# SCH_MODULO_CO2_Ver_1_0__2023-02-25.net
KiCad netlist of a schematic drawn in EasyEDA
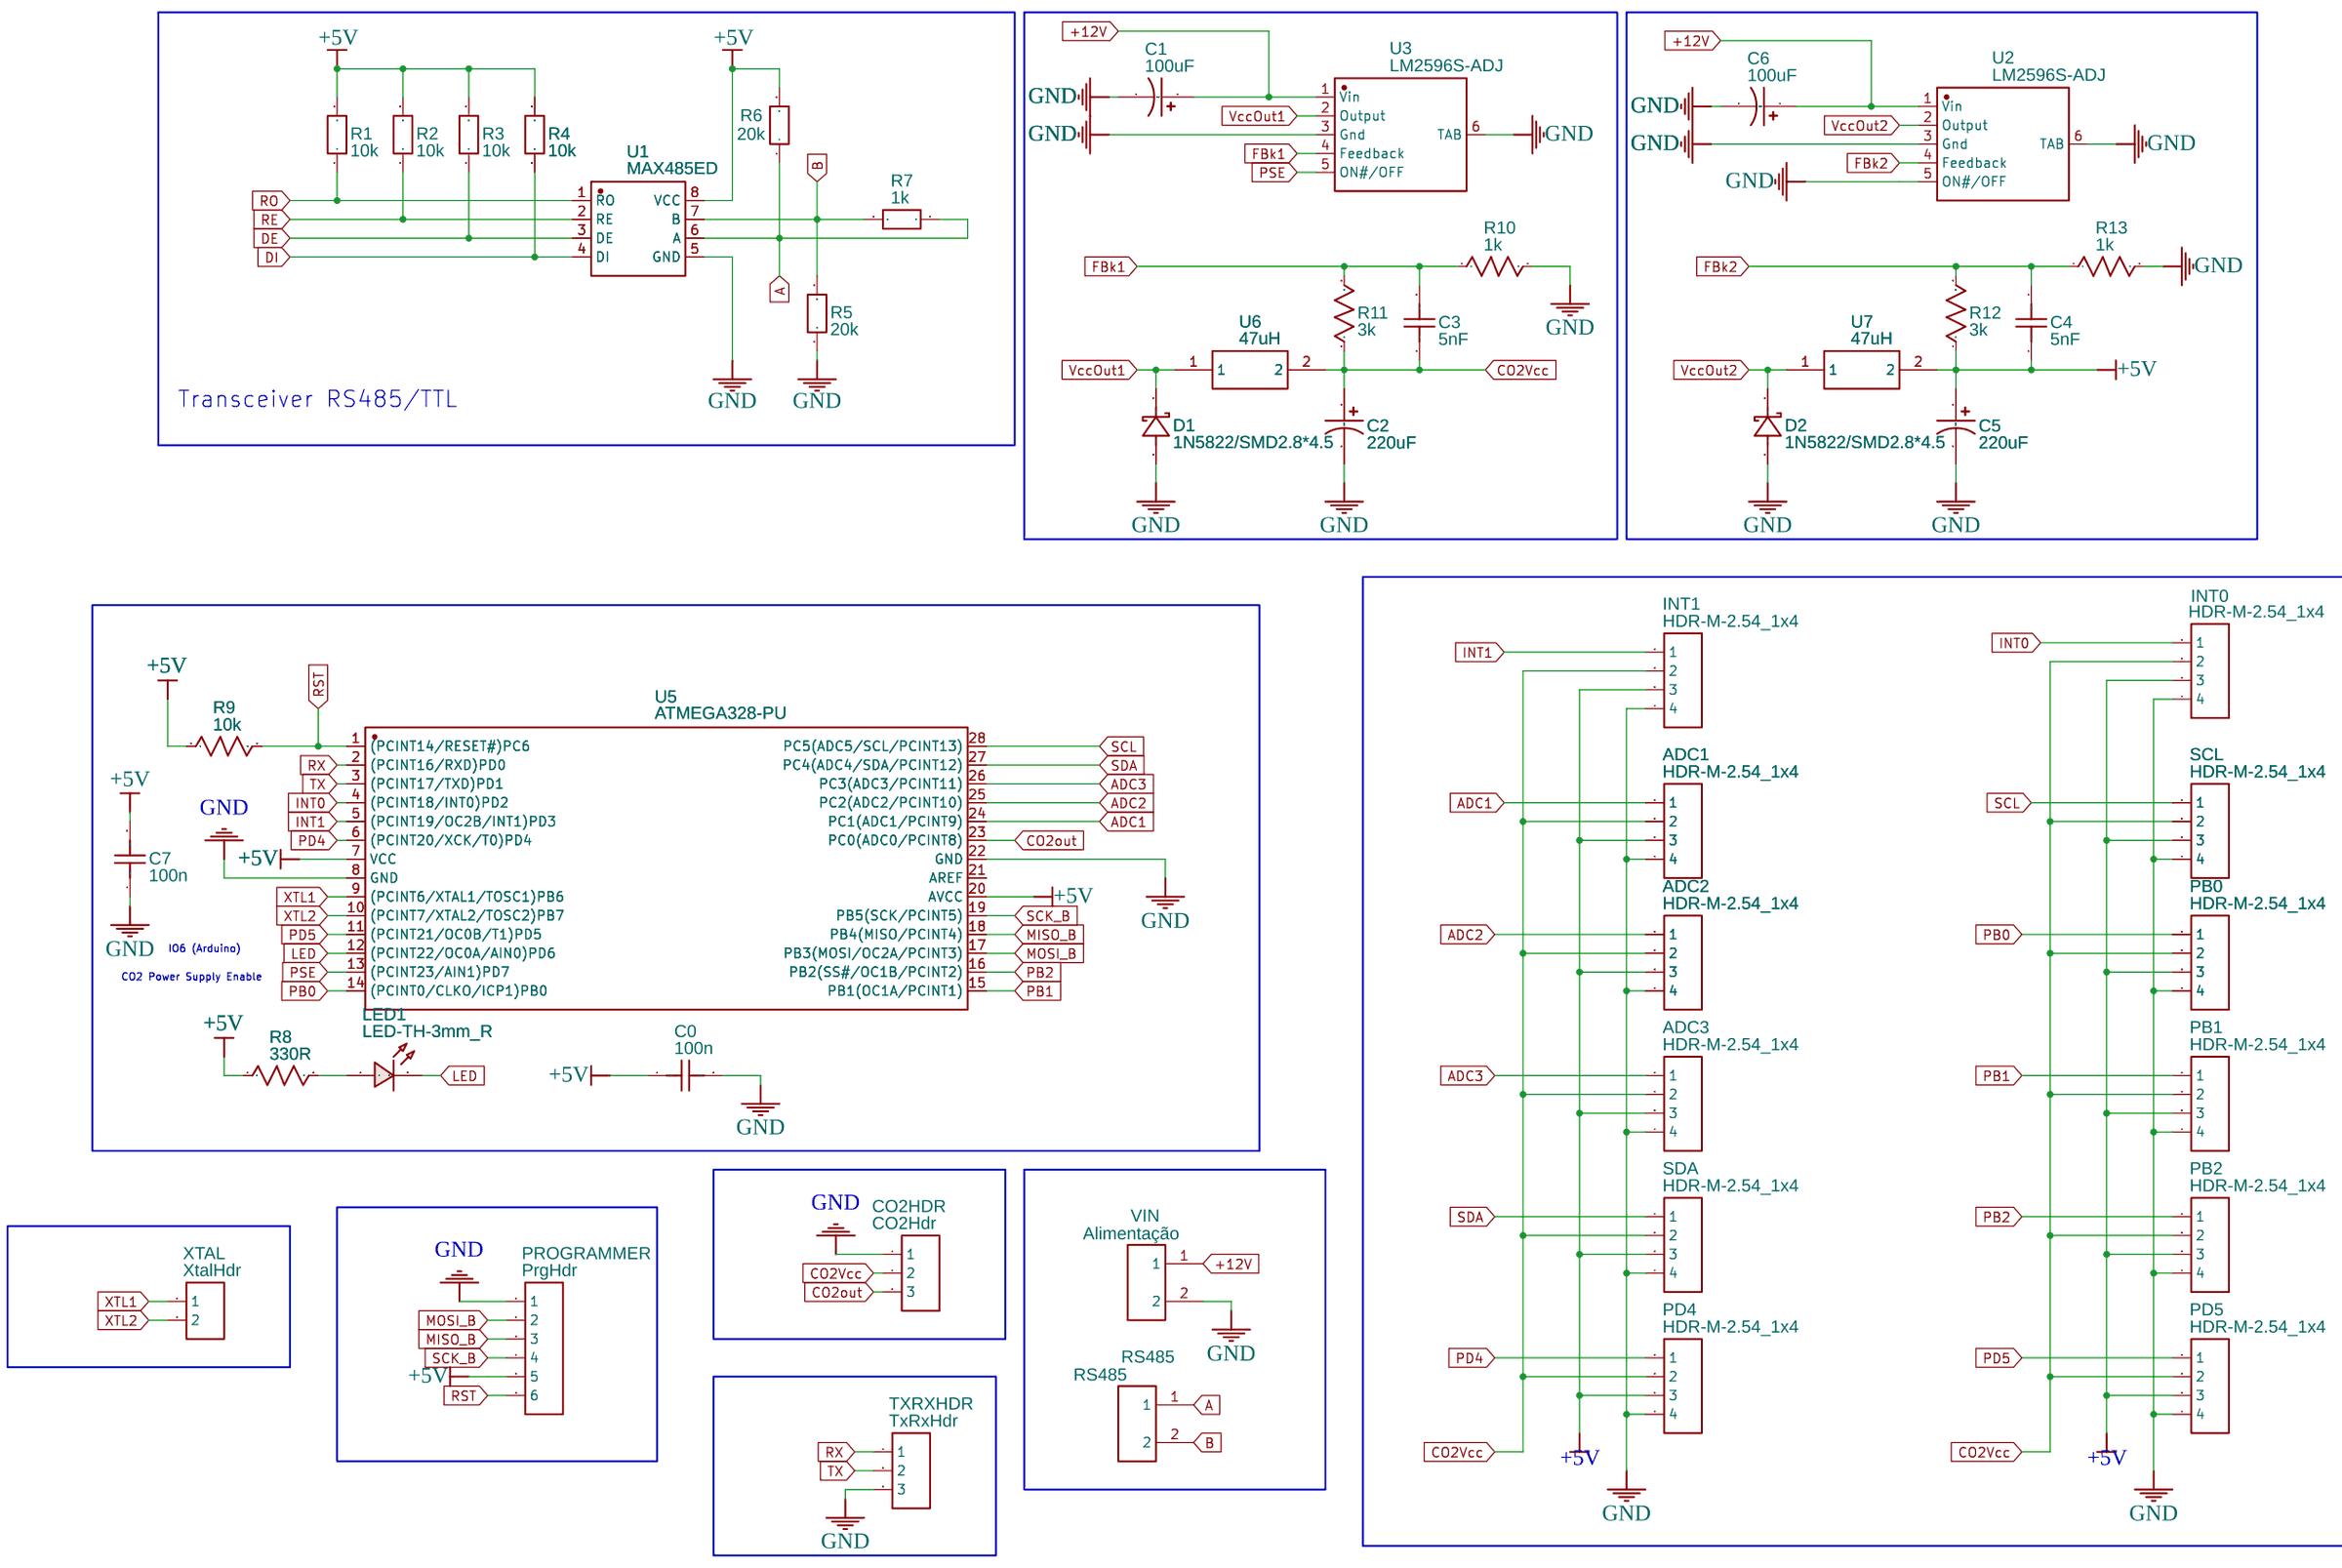
[diagram p0: schematic sheet]

(export (version "E")
  (design (tool "Eeschema 10.0.6"))
  (components
    (comp (ref "ADC1")
      (value "HDR-M-2.54_1x4")
      (fields (field (name "BOM_Supplier Part") "C124378"))
      (libsource (lib "") (part "HDR-M-2.54_1x4_2"))
    )
    (comp (ref "ADC2")
      (value "HDR-M-2.54_1x4")
      (fields (field (name "BOM_Supplier Part") "C124378"))
      (libsource (lib "") (part "HDR-M-2.54_1x4_2"))
    )
    (comp (ref "ADC3")
      (value "HDR-M-2.54_1x4")
      (fields (field (name "BOM_Supplier Part") "C124378"))
      (libsource (lib "") (part "HDR-M-2.54_1x4_2"))
    )
    (comp (ref "C0") (value "100n") (libsource (lib "") (part "C_RAD-0.1_US")))
    (comp (ref "C1") (value "100uF") (libsource (lib "") (part "CE_TH_D6.3×F2.5_US_1")))
    (comp (ref "C2") (value "220uF") (libsource (lib "") (part "CE_TH_D6.3×F2.5_US")))
    (comp (ref "C3") (value "5nF") (libsource (lib "") (part "C_0603_US")))
    (comp (ref "C4") (value "5nF") (libsource (lib "") (part "C_0603_US")))
    (comp (ref "C5") (value "220uF") (libsource (lib "") (part "CE_TH_D6.3×F2.5_US")))
    (comp (ref "C6") (value "100uF") (libsource (lib "") (part "CE_TH_D6.3×F2.5_US_1")))
    (comp (ref "C7") (value "100n") (libsource (lib "") (part "C_0603_US")))
    (comp (ref "CO2HDR")
      (value "CO2Hdr")
      (fields (field (name "BOM_Supplier Part") "C146690"))
      (libsource (lib "") (part "HDR-F-2.54_1x3_1"))
    )
    (comp (ref "D1")
      (value "1N5822/SMD2.8*4.5")
      (fields (field (name "BOM_Supplier Part") "C9900015672"))
      (libsource (lib "") (part "1N5822/SMD2.8*4.5"))
    )
    (comp (ref "D2")
      (value "1N5822/SMD2.8*4.5")
      (fields (field (name "BOM_Supplier Part") "C9900015672"))
      (libsource (lib "") (part "1N5822/SMD2.8*4.5"))
    )
    (comp (ref "INT0")
      (value "HDR-M-2.54_1x4")
      (fields (field (name "BOM_Supplier Part") "C124378"))
      (libsource (lib "") (part "HDR-M-2.54_1x4_1"))
    )
    (comp (ref "INT1")
      (value "HDR-M-2.54_1x4")
      (fields (field (name "BOM_Supplier Part") "C124378"))
      (libsource (lib "") (part "HDR-M-2.54_1x4_1"))
    )
    (comp (ref "LED1")
      (value "LED-TH-3mm_R")
      (fields
        (field (name "BOM_Manufacturer Part") "204-10SDRD/S530-A3-L")
        (field (name "BOM_Supplier Part") "C84774")
      )
      (libsource (lib "") (part "LED-TH-3mm_R"))
    )
    (comp (ref "PB0")
      (value "HDR-M-2.54_1x4")
      (fields (field (name "BOM_Supplier Part") "C124378"))
      (libsource (lib "") (part "HDR-M-2.54_1x4_4"))
    )
    (comp (ref "PB1")
      (value "HDR-M-2.54_1x4")
      (fields (field (name "BOM_Supplier Part") "C124378"))
      (libsource (lib "") (part "HDR-M-2.54_1x4_4"))
    )
    (comp (ref "PB2")
      (value "HDR-M-2.54_1x4")
      (fields (field (name "BOM_Supplier Part") "C124378"))
      (libsource (lib "") (part "HDR-M-2.54_1x4_4"))
    )
    (comp (ref "PD4")
      (value "HDR-M-2.54_1x4")
      (fields (field (name "BOM_Supplier Part") "C124378"))
      (libsource (lib "") (part "HDR-M-2.54_1x4_3"))
    )
    (comp (ref "PD5")
      (value "HDR-M-2.54_1x4")
      (fields (field (name "BOM_Supplier Part") "C124378"))
      (libsource (lib "") (part "HDR-M-2.54_1x4_3"))
    )
    (comp (ref "PROGRAMMER")
      (value "PrgHdr")
      (fields (field (name "BOM_Supplier Part") "C40877"))
      (libsource (lib "") (part "HDR-F-2.54_1x6"))
    )
    (comp (ref "R1") (value "10k") (libsource (lib "") (part "R_1206_EU")))
    (comp (ref "R2") (value "10k") (libsource (lib "") (part "R_1206_EU")))
    (comp (ref "R3") (value "10k") (libsource (lib "") (part "R_1206_EU")))
    (comp (ref "R4") (value "10k") (libsource (lib "") (part "R_1206_EU")))
    (comp (ref "R5") (value "20k") (libsource (lib "") (part "R_1206_EU")))
    (comp (ref "R6") (value "20k") (libsource (lib "") (part "R_1206_EU")))
    (comp (ref "R7") (value "1k") (libsource (lib "") (part "R_1206_EU_1")))
    (comp (ref "R8") (value "330R") (libsource (lib "") (part "R_AXIAL-0.3_US")))
    (comp (ref "R9") (value "10k") (libsource (lib "") (part "R_AXIAL-0.3_US")))
    (comp (ref "R10") (value "1k") (libsource (lib "") (part "R_1206_US")))
    (comp (ref "R11") (value "3k") (libsource (lib "") (part "R_1206_US_1")))
    (comp (ref "R12") (value "3k") (libsource (lib "") (part "R_1206_US_1")))
    (comp (ref "R13") (value "1k") (libsource (lib "") (part "R_1206_US")))
    (comp (ref "RS485") (value "RS485") (libsource (lib "") (part "conector verde 2 pinos")))
    (comp (ref "SCL")
      (value "HDR-M-2.54_1x4")
      (fields (field (name "BOM_Supplier Part") "C124378"))
      (libsource (lib "") (part "HDR-M-2.54_1x4_5"))
    )
    (comp (ref "SDA")
      (value "HDR-M-2.54_1x4")
      (fields (field (name "BOM_Supplier Part") "C124378"))
      (libsource (lib "") (part "HDR-M-2.54_1x4"))
    )
    (comp (ref "TXRXHDR")
      (value "TxRxHdr")
      (fields (field (name "BOM_Supplier Part") "C146690"))
      (libsource (lib "") (part "HDR-F-2.54_1x3"))
    )
    (comp (ref "U1")
      (value "MAX485ED")
      (fields (field (name "BOM_Supplier Part") "C481667"))
      (libsource (lib "") (part "MAX485ED"))
    )
    (comp (ref "U2")
      (value "LM2596S-ADJ")
      (fields (field (name "BOM_Supplier Part") "C347423"))
      (libsource (lib "") (part "LM2596S-ADJ"))
    )
    (comp (ref "U3")
      (value "LM2596S-ADJ")
      (fields (field (name "BOM_Supplier Part") "C347423"))
      (libsource (lib "") (part "LM2596S-ADJ"))
    )
    (comp (ref "U5")
      (value "ATMEGA328-PU")
      (fields (field (name "BOM_Supplier Part") "C613508"))
      (libsource (lib "") (part "ATMEGA328-PU"))
    )
    (comp (ref "U6") (value "47uH") (libsource (lib "") (part "smd_inductor_big")))
    (comp (ref "U7") (value "47uH") (libsource (lib "") (part "smd_inductor_big")))
    (comp (ref "VIN") (value "Alimentação") (libsource (lib "") (part "conector verde 2 pinos_1")))
    (comp (ref "XTAL")
      (value "XtalHdr")
      (fields (field (name "BOM_Supplier Part") "C49661"))
      (libsource (lib "") (part "HDR-F-2.54_1x2"))
    )
  )
  (nets
    (net (code "1") (name "+5V") (class "Default")
      (node (ref "ADC1") (pin "3") (pinfunction "3_3") (pintype "unspecified"))
      (node (ref "ADC2") (pin "3") (pinfunction "3_3") (pintype "unspecified"))
      (node (ref "ADC3") (pin "3") (pinfunction "3_3") (pintype "unspecified"))
      (node (ref "C0") (pin "1") (pinfunction "1_1") (pintype "unspecified"))
      (node (ref "C4") (pin "1") (pinfunction "1_1") (pintype "unspecified"))
      (node (ref "C5") (pin "1") (pinfunction "1_1") (pintype "unspecified"))
      (node (ref "C7") (pin "2") (pinfunction "2_2") (pintype "unspecified"))
      (node (ref "INT0") (pin "3") (pinfunction "3_3") (pintype "unspecified"))
      (node (ref "INT1") (pin "3") (pinfunction "3_3") (pintype "unspecified"))
      (node (ref "PB0") (pin "3") (pinfunction "3_3") (pintype "unspecified"))
      (node (ref "PB1") (pin "3") (pinfunction "3_3") (pintype "unspecified"))
      (node (ref "PB2") (pin "3") (pinfunction "3_3") (pintype "unspecified"))
      (node (ref "PD4") (pin "3") (pinfunction "3_3") (pintype "unspecified"))
      (node (ref "PD5") (pin "3") (pinfunction "3_3") (pintype "unspecified"))
      (node (ref "PROGRAMMER") (pin "5") (pinfunction "5_5") (pintype "input"))
      (node (ref "R1") (pin "2") (pinfunction "2_2") (pintype "unspecified"))
      (node (ref "R12") (pin "1") (pinfunction "1_1") (pintype "unspecified"))
      (node (ref "R2") (pin "2") (pinfunction "2_2") (pintype "unspecified"))
      (node (ref "R3") (pin "2") (pinfunction "2_2") (pintype "unspecified"))
      (node (ref "R4") (pin "2") (pinfunction "2_2") (pintype "unspecified"))
      (node (ref "R6") (pin "2") (pinfunction "2_2") (pintype "unspecified"))
      (node (ref "R8") (pin "1") (pinfunction "1_1") (pintype "unspecified"))
      (node (ref "R9") (pin "1") (pinfunction "1_1") (pintype "unspecified"))
      (node (ref "SCL") (pin "3") (pinfunction "3_3") (pintype "unspecified"))
      (node (ref "SDA") (pin "3") (pinfunction "3_3") (pintype "unspecified"))
      (node (ref "U1") (pin "8") (pinfunction "VCC_8") (pintype "unspecified"))
      (node (ref "U5") (pin "20") (pinfunction "AVCC_20") (pintype "unspecified"))
      (node (ref "U5") (pin "7") (pinfunction "VCC_7") (pintype "unspecified"))
      (node (ref "U7") (pin "2") (pinfunction "2_2") (pintype "unspecified"))
    )
    (net (code "2") (name "+12V") (class "Default")
      (node (ref "C1") (pin "1") (pinfunction "1_1") (pintype "unspecified"))
      (node (ref "C6") (pin "1") (pinfunction "1_1") (pintype "unspecified"))
      (node (ref "U2") (pin "1") (pinfunction "Vin_1") (pintype "unspecified"))
      (node (ref "U3") (pin "1") (pinfunction "Vin_1") (pintype "unspecified"))
      (node (ref "VIN") (pin "1") (pinfunction "1_1") (pintype "unspecified"))
    )
    (net (code "3") (name "A") (class "Default")
      (node (ref "R6") (pin "1") (pinfunction "1_1") (pintype "unspecified"))
      (node (ref "R7") (pin "1") (pinfunction "1_1") (pintype "unspecified"))
      (node (ref "RS485") (pin "1") (pinfunction "1_1") (pintype "unspecified"))
      (node (ref "U1") (pin "6") (pinfunction "A_6") (pintype "unspecified"))
    )
    (net (code "4") (name "ADC1") (class "Default")
      (node (ref "ADC1") (pin "1") (pinfunction "1_1") (pintype "unspecified"))
      (node (ref "U5") (pin "24") (pinfunction "PC1(ADC1/PCINT9)_24") (pintype "unspecified"))
    )
    (net (code "5") (name "ADC2") (class "Default")
      (node (ref "ADC2") (pin "1") (pinfunction "1_1") (pintype "unspecified"))
      (node (ref "U5") (pin "25") (pinfunction "PC2(ADC2/PCINT10)_25") (pintype "unspecified"))
    )
    (net (code "6") (name "ADC3") (class "Default")
      (node (ref "ADC3") (pin "1") (pinfunction "1_1") (pintype "unspecified"))
      (node (ref "U5") (pin "26") (pinfunction "PC3(ADC3/PCINT11)_26") (pintype "unspecified"))
    )
    (net (code "7") (name "B") (class "Default")
      (node (ref "R5") (pin "2") (pinfunction "2_2") (pintype "unspecified"))
      (node (ref "R7") (pin "2") (pinfunction "2_2") (pintype "unspecified"))
      (node (ref "RS485") (pin "2") (pinfunction "2_2") (pintype "unspecified"))
      (node (ref "U1") (pin "7") (pinfunction "B_7") (pintype "unspecified"))
    )
    (net (code "8") (name "CO2Vcc") (class "Default")
      (node (ref "ADC1") (pin "2") (pinfunction "2_2") (pintype "unspecified"))
      (node (ref "ADC2") (pin "2") (pinfunction "2_2") (pintype "unspecified"))
      (node (ref "ADC3") (pin "2") (pinfunction "2_2") (pintype "unspecified"))
      (node (ref "C2") (pin "1") (pinfunction "1_1") (pintype "unspecified"))
      (node (ref "C3") (pin "1") (pinfunction "1_1") (pintype "unspecified"))
      (node (ref "CO2HDR") (pin "2") (pinfunction "2_2") (pintype "input"))
      (node (ref "INT0") (pin "2") (pinfunction "2_2") (pintype "unspecified"))
      (node (ref "INT1") (pin "2") (pinfunction "2_2") (pintype "unspecified"))
      (node (ref "PB0") (pin "2") (pinfunction "2_2") (pintype "unspecified"))
      (node (ref "PB1") (pin "2") (pinfunction "2_2") (pintype "unspecified"))
      (node (ref "PB2") (pin "2") (pinfunction "2_2") (pintype "unspecified"))
      (node (ref "PD4") (pin "2") (pinfunction "2_2") (pintype "unspecified"))
      (node (ref "PD5") (pin "2") (pinfunction "2_2") (pintype "unspecified"))
      (node (ref "R11") (pin "1") (pinfunction "1_1") (pintype "unspecified"))
      (node (ref "SCL") (pin "2") (pinfunction "2_2") (pintype "unspecified"))
      (node (ref "SDA") (pin "2") (pinfunction "2_2") (pintype "unspecified"))
      (node (ref "U6") (pin "2") (pinfunction "2_2") (pintype "unspecified"))
    )
    (net (code "9") (name "CO2out") (class "Default")
      (node (ref "CO2HDR") (pin "3") (pinfunction "3_3") (pintype "input"))
      (node (ref "U5") (pin "23") (pinfunction "PC0(ADC0/PCINT8)_23") (pintype "unspecified"))
    )
    (net (code "10") (name "DE") (class "Default")
      (node (ref "R3") (pin "1") (pinfunction "1_1") (pintype "unspecified"))
      (node (ref "U1") (pin "3") (pinfunction "DE_3") (pintype "unspecified"))
    )
    (net (code "11") (name "DI") (class "Default")
      (node (ref "R4") (pin "1") (pinfunction "1_1") (pintype "unspecified"))
      (node (ref "U1") (pin "4") (pinfunction "DI_4") (pintype "unspecified"))
    )
    (net (code "12") (name "FBk1") (class "Default")
      (node (ref "C3") (pin "2") (pinfunction "2_2") (pintype "unspecified"))
      (node (ref "R10") (pin "1") (pinfunction "1_1") (pintype "unspecified"))
      (node (ref "R11") (pin "2") (pinfunction "2_2") (pintype "unspecified"))
      (node (ref "U3") (pin "4") (pinfunction "Feedback_4") (pintype "unspecified"))
    )
    (net (code "13") (name "FBk2") (class "Default")
      (node (ref "C4") (pin "2") (pinfunction "2_2") (pintype "unspecified"))
      (node (ref "R12") (pin "2") (pinfunction "2_2") (pintype "unspecified"))
      (node (ref "R13") (pin "1") (pinfunction "1_1") (pintype "unspecified"))
      (node (ref "U2") (pin "4") (pinfunction "Feedback_4") (pintype "unspecified"))
    )
    (net (code "14") (name "GND") (class "Default")
      (node (ref "ADC1") (pin "4") (pinfunction "4_4") (pintype "unspecified"))
      (node (ref "ADC2") (pin "4") (pinfunction "4_4") (pintype "unspecified"))
      (node (ref "ADC3") (pin "4") (pinfunction "4_4") (pintype "unspecified"))
      (node (ref "C0") (pin "2") (pinfunction "2_2") (pintype "unspecified"))
      (node (ref "C1") (pin "2") (pinfunction "2_2") (pintype "unspecified"))
      (node (ref "C2") (pin "2") (pinfunction "2_2") (pintype "unspecified"))
      (node (ref "C5") (pin "2") (pinfunction "2_2") (pintype "unspecified"))
      (node (ref "C6") (pin "2") (pinfunction "2_2") (pintype "unspecified"))
      (node (ref "C7") (pin "1") (pinfunction "1_1") (pintype "unspecified"))
      (node (ref "CO2HDR") (pin "1") (pinfunction "1_1") (pintype "input"))
      (node (ref "D1") (pin "2") (pinfunction "K_2") (pintype "unspecified"))
      (node (ref "D2") (pin "2") (pinfunction "K_2") (pintype "unspecified"))
      (node (ref "INT0") (pin "4") (pinfunction "4_4") (pintype "unspecified"))
      (node (ref "INT1") (pin "4") (pinfunction "4_4") (pintype "unspecified"))
      (node (ref "PB0") (pin "4") (pinfunction "4_4") (pintype "unspecified"))
      (node (ref "PB1") (pin "4") (pinfunction "4_4") (pintype "unspecified"))
      (node (ref "PB2") (pin "4") (pinfunction "4_4") (pintype "unspecified"))
      (node (ref "PD4") (pin "4") (pinfunction "4_4") (pintype "unspecified"))
      (node (ref "PD5") (pin "4") (pinfunction "4_4") (pintype "unspecified"))
      (node (ref "PROGRAMMER") (pin "1") (pinfunction "1_1") (pintype "input"))
      (node (ref "R10") (pin "2") (pinfunction "2_2") (pintype "unspecified"))
      (node (ref "R13") (pin "2") (pinfunction "2_2") (pintype "unspecified"))
      (node (ref "R5") (pin "1") (pinfunction "1_1") (pintype "unspecified"))
      (node (ref "SCL") (pin "4") (pinfunction "4_4") (pintype "unspecified"))
      (node (ref "SDA") (pin "4") (pinfunction "4_4") (pintype "unspecified"))
      (node (ref "TXRXHDR") (pin "3") (pinfunction "3_3") (pintype "input"))
      (node (ref "U1") (pin "5") (pinfunction "GND_5") (pintype "unspecified"))
      (node (ref "U2") (pin "3") (pinfunction "Gnd_3") (pintype "unspecified"))
      (node (ref "U2") (pin "5") (pinfunction "ON#/OFF_5") (pintype "unspecified"))
      (node (ref "U2") (pin "6") (pinfunction "TAB_6") (pintype "unspecified"))
      (node (ref "U3") (pin "3") (pinfunction "Gnd_3") (pintype "unspecified"))
      (node (ref "U3") (pin "6") (pinfunction "TAB_6") (pintype "unspecified"))
      (node (ref "U5") (pin "22") (pinfunction "GND_22") (pintype "unspecified"))
      (node (ref "U5") (pin "8") (pinfunction "GND_8") (pintype "unspecified"))
      (node (ref "VIN") (pin "2") (pinfunction "2_2") (pintype "unspecified"))
    )
    (net (code "15") (name "INT0") (class "Default")
      (node (ref "INT0") (pin "1") (pinfunction "1_1") (pintype "unspecified"))
      (node (ref "U5") (pin "4") (pinfunction "(PCINT18/INT0)PD2_4") (pintype "unspecified"))
    )
    (net (code "16") (name "INT1") (class "Default")
      (node (ref "INT1") (pin "1") (pinfunction "1_1") (pintype "unspecified"))
      (node (ref "U5") (pin "5") (pinfunction "(PCINT19/OC2B/INT1)PD3_5") (pintype "unspecified"))
    )
    (net (code "17") (name "LED") (class "Default")
      (node (ref "LED1") (pin "2") (pinfunction "2_2") (pintype "unspecified"))
      (node (ref "U5") (pin "12") (pinfunction "(PCINT22/OC0A/AIN0)PD6_12") (pintype "unspecified"))
    )
    (net (code "18") (name "MISO_B") (class "Default")
      (node (ref "PROGRAMMER") (pin "3") (pinfunction "3_3") (pintype "input"))
      (node (ref "U5") (pin "18") (pinfunction "PB4(MISO/PCINT4)_18") (pintype "unspecified"))
    )
    (net (code "19") (name "MOSI_B") (class "Default")
      (node (ref "PROGRAMMER") (pin "2") (pinfunction "2_2") (pintype "input"))
      (node (ref "U5") (pin "17") (pinfunction "PB3(MOSI/OC2A/PCINT3)_17") (pintype "unspecified"))
    )
    (net (code "20") (name "Net-(LED1-Pad1)") (class "Default")
      (node (ref "LED1") (pin "1") (pinfunction "1_1") (pintype "unspecified"))
      (node (ref "R8") (pin "2") (pinfunction "2_2") (pintype "unspecified"))
    )
    (net (code "21") (name "PB0") (class "Default")
      (node (ref "PB0") (pin "1") (pinfunction "1_1") (pintype "unspecified"))
      (node (ref "U5") (pin "14") (pinfunction "(PCINT0/CLKO/ICP1)PB0_14") (pintype "unspecified"))
    )
    (net (code "22") (name "PB1") (class "Default")
      (node (ref "PB1") (pin "1") (pinfunction "1_1") (pintype "unspecified"))
      (node (ref "U5") (pin "15") (pinfunction "PB1(OC1A/PCINT1)_15") (pintype "unspecified"))
    )
    (net (code "23") (name "PB2") (class "Default")
      (node (ref "PB2") (pin "1") (pinfunction "1_1") (pintype "unspecified"))
      (node (ref "U5") (pin "16") (pinfunction "PB2(SS#/OC1B/PCINT2)_16") (pintype "unspecified"))
    )
    (net (code "24") (name "PD4") (class "Default")
      (node (ref "PD4") (pin "1") (pinfunction "1_1") (pintype "unspecified"))
      (node (ref "U5") (pin "6") (pinfunction "(PCINT20/XCK/T0)PD4_6") (pintype "unspecified"))
    )
    (net (code "25") (name "PD5") (class "Default")
      (node (ref "PD5") (pin "1") (pinfunction "1_1") (pintype "unspecified"))
      (node (ref "U5") (pin "11") (pinfunction "(PCINT21/OC0B/T1)PD5_11") (pintype "unspecified"))
    )
    (net (code "26") (name "PSE") (class "Default")
      (node (ref "U3") (pin "5") (pinfunction "ON#/OFF_5") (pintype "unspecified"))
      (node (ref "U5") (pin "13") (pinfunction "(PCINT23/AIN1)PD7_13") (pintype "unspecified"))
    )
    (net (code "27") (name "RE") (class "Default")
      (node (ref "R2") (pin "1") (pinfunction "1_1") (pintype "unspecified"))
      (node (ref "U1") (pin "2") (pinfunction "RE_2") (pintype "unspecified"))
    )
    (net (code "28") (name "RO") (class "Default")
      (node (ref "R1") (pin "1") (pinfunction "1_1") (pintype "unspecified"))
      (node (ref "U1") (pin "1") (pinfunction "RO_1") (pintype "unspecified"))
    )
    (net (code "29") (name "RST") (class "Default")
      (node (ref "PROGRAMMER") (pin "6") (pinfunction "6_6") (pintype "input"))
      (node (ref "R9") (pin "2") (pinfunction "2_2") (pintype "unspecified"))
      (node (ref "U5") (pin "1") (pinfunction "(PCINT14/RESET#)PC6_1") (pintype "unspecified"))
    )
    (net (code "30") (name "RX") (class "Default")
      (node (ref "TXRXHDR") (pin "1") (pinfunction "1_1") (pintype "input"))
      (node (ref "U5") (pin "2") (pinfunction "(PCINT16/RXD)PD0_2") (pintype "unspecified"))
    )
    (net (code "31") (name "SCK_B") (class "Default")
      (node (ref "PROGRAMMER") (pin "4") (pinfunction "4_4") (pintype "input"))
      (node (ref "U5") (pin "19") (pinfunction "PB5(SCK/PCINT5)_19") (pintype "unspecified"))
    )
    (net (code "32") (name "SCL") (class "Default")
      (node (ref "SCL") (pin "1") (pinfunction "1_1") (pintype "unspecified"))
      (node (ref "U5") (pin "28") (pinfunction "PC5(ADC5/SCL/PCINT13)_28") (pintype "unspecified"))
    )
    (net (code "33") (name "SDA") (class "Default")
      (node (ref "SDA") (pin "1") (pinfunction "1_1") (pintype "unspecified"))
      (node (ref "U5") (pin "27") (pinfunction "PC4(ADC4/SDA/PCINT12)_27") (pintype "unspecified"))
    )
    (net (code "34") (name "TX") (class "Default")
      (node (ref "TXRXHDR") (pin "2") (pinfunction "2_2") (pintype "input"))
      (node (ref "U5") (pin "3") (pinfunction "(PCINT17/TXD)PD1_3") (pintype "unspecified"))
    )
    (net (code "35") (name "VccOut1") (class "Default")
      (node (ref "D1") (pin "1") (pinfunction "A_1") (pintype "unspecified"))
      (node (ref "U3") (pin "2") (pinfunction "Output_2") (pintype "unspecified"))
      (node (ref "U6") (pin "1") (pinfunction "1_1") (pintype "unspecified"))
    )
    (net (code "36") (name "VccOut2") (class "Default")
      (node (ref "D2") (pin "1") (pinfunction "A_1") (pintype "unspecified"))
      (node (ref "U2") (pin "2") (pinfunction "Output_2") (pintype "unspecified"))
      (node (ref "U7") (pin "1") (pinfunction "1_1") (pintype "unspecified"))
    )
    (net (code "37") (name "XTL1") (class "Default")
      (node (ref "U5") (pin "9") (pinfunction "(PCINT6/XTAL1/TOSC1)PB6_9") (pintype "unspecified"))
      (node (ref "XTAL") (pin "1") (pinfunction "1_1") (pintype "input"))
    )
    (net (code "38") (name "XTL2") (class "Default")
      (node (ref "U5") (pin "10") (pinfunction "(PCINT7/XTAL2/TOSC2)PB7_10") (pintype "unspecified"))
      (node (ref "XTAL") (pin "2") (pinfunction "2_2") (pintype "input"))
    )
    (net (code "39") (name "unconnected-(U5-AREF-Pad21)") (class "Default")
      (node (ref "U5") (pin "21") (pinfunction "AREF_21") (pintype "unspecified"))
    )
  )
)
